# Control_Board.net
KiCad netlist of a schematic drawn in EAGLE
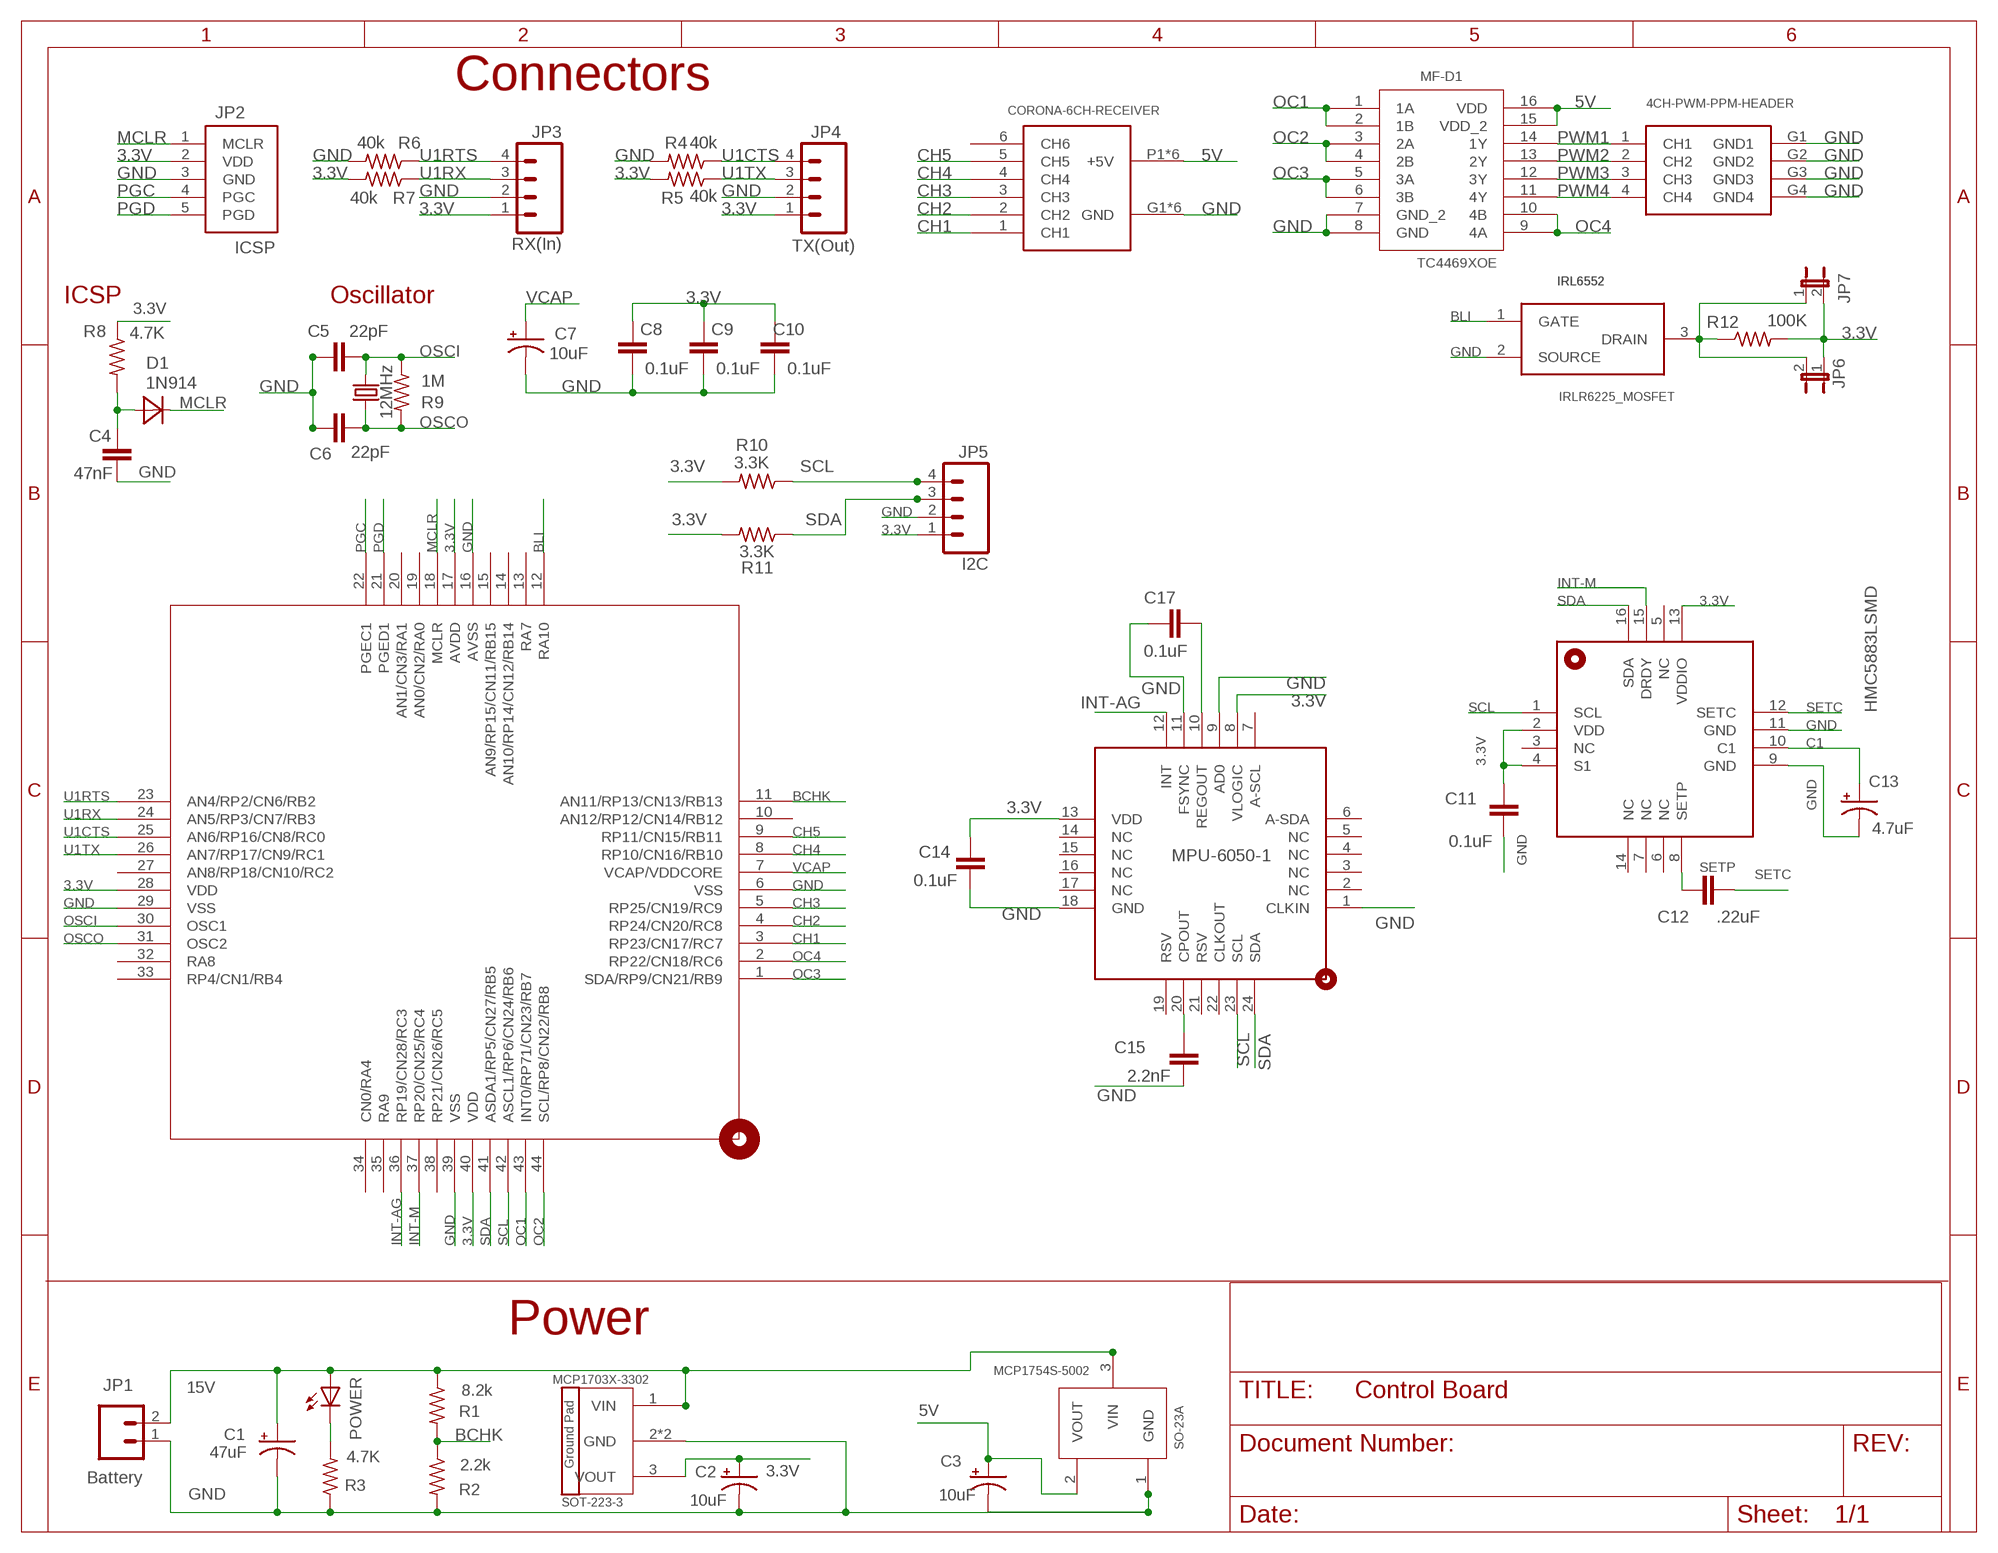
[diagram p0: schematic, sheet 1]

(export (version "E")
  (design (tool "Eeschema 10.0.6"))
  (components
    (comp (ref "C1")
      (value "47uF")
      (footprint "eagle-import:E2-5")
      (libsource (lib "eagle-import") (part "CPOL-USE2-5"))
    )
    (comp (ref "C2")
      (value "10uF")
      (footprint "eagle-import:E2-5")
      (libsource (lib "eagle-import") (part "CPOL-USE2-5"))
    )
    (comp (ref "C3")
      (value "10uF")
      (footprint "eagle-import:E2-5")
      (libsource (lib "eagle-import") (part "CPOL-USE2-5"))
    )
    (comp (ref "C4")
      (value "47nF")
      (footprint "eagle-import:CAP-SMALL-2MM-SMALLPAD")
      (libsource (lib "eagle-import") (part "CAPACITOR"))
    )
    (comp (ref "C5")
      (value "22pF")
      (footprint "eagle-import:CAP-SMALL-2MM-SMALLPAD")
      (libsource (lib "eagle-import") (part "CAPACITOR"))
    )
    (comp (ref "C6")
      (value "22pF")
      (footprint "eagle-import:CAP-SMALL-2MM-SMALLPAD")
      (libsource (lib "eagle-import") (part "CAPACITOR"))
    )
    (comp (ref "C7")
      (value "10uF")
      (footprint "eagle-import:E2-5")
      (libsource (lib "eagle-import") (part "CPOL-USE2-5"))
    )
    (comp (ref "C8")
      (value "0.1uF")
      (footprint "eagle-import:CAP-SMALL-2MM-SMALLPAD")
      (libsource (lib "eagle-import") (part "CAPACITOR"))
    )
    (comp (ref "C9")
      (value "0.1uF")
      (footprint "eagle-import:CAP-SMALL-2MM-SMALLPAD")
      (libsource (lib "eagle-import") (part "CAPACITOR"))
    )
    (comp (ref "C10")
      (value "0.1uF")
      (footprint "eagle-import:CAP-SMALL-2MM-SMALLPAD")
      (libsource (lib "eagle-import") (part "CAPACITOR"))
    )
    (comp (ref "C11")
      (value "0.1uF")
      (footprint "eagle-import:CAP-SMALL-2MM-SMALLPAD")
      (libsource (lib "eagle-import") (part "CAPACITOR"))
    )
    (comp (ref "C12")
      (value ".22uF")
      (footprint "eagle-import:C050-024X044")
      (libsource (lib "eagle-import") (part "C-EU050-024X044"))
    )
    (comp (ref "C13")
      (value "4.7uF")
      (footprint "eagle-import:E2-5")
      (libsource (lib "eagle-import") (part "CPOL-USE2-5"))
    )
    (comp (ref "C14")
      (value "0.1uF")
      (footprint "eagle-import:CAP-SMALL-2MM-SMALLPAD")
      (libsource (lib "eagle-import") (part "CAPACITOR"))
    )
    (comp (ref "C15")
      (value "2.2nF")
      (footprint "eagle-import:CAP-SMALL-2MM-SMALLPAD")
      (libsource (lib "eagle-import") (part "CAPACITOR"))
    )
    (comp (ref "C17")
      (value "0.1uF")
      (footprint "eagle-import:CAP-SMALL-2MM-SMALLPAD")
      (libsource (lib "eagle-import") (part "CAPACITOR"))
    )
    (comp (ref "CR1")
      (value "CORONA-6CH-RECEIVER")
      (footprint "eagle-import:CORONA-6CH-RECEIVER-FOOTPRINT")
      (libsource (lib "eagle-import") (part "CORONA-6CH-RECEIVER"))
    )
    (comp (ref "D1")
      (value "1N914")
      (footprint "eagle-import:DO34-5")
      (libsource (lib "eagle-import") (part "1N914"))
    )
    (comp (ref "IRL6552")
      (value "IRLR6225_MOSFET")
      (footprint "eagle-import:TO252")
      (libsource (lib "eagle-import") (part "IRLR6225_MOSFET"))
    )
    (comp (ref "JP1")
      (value "Battery")
      (footprint "eagle-import:1X02_LONGPADS")
      (libsource (lib "eagle-import") (part "M02"))
    )
    (comp (ref "JP2")
      (value "ICSP")
      (footprint "eagle-import:ICSP_LOCK_LONGPADS")
      (libsource (lib "eagle-import") (part "ICSPPADS"))
    )
    (comp (ref "JP3")
      (value "RX(In)")
      (footprint "eagle-import:1X04_LOCK_LONGPADS")
      (libsource (lib "eagle-import") (part "M04LOCK_LONGPADS"))
    )
    (comp (ref "JP4")
      (value "TX(Out)")
      (footprint "eagle-import:1X04_LOCK_LONGPADS")
      (libsource (lib "eagle-import") (part "M04LOCK_LONGPADS"))
    )
    (comp (ref "JP5")
      (value "I2C")
      (footprint "eagle-import:1X04_LOCK_LONGPADS")
      (libsource (lib "eagle-import") (part "M04LOCK_LONGPADS"))
    )
    (comp (ref "JP6")
      (value "JUMPER-2PTH_LOCK")
      (footprint "eagle-import:1X02_LOCK")
      (libsource (lib "eagle-import") (part "JUMPER-2PTH_LOCK"))
    )
    (comp (ref "JP7")
      (value "JUMPER-2PTH_LOCK")
      (footprint "eagle-import:1X02_LOCK")
      (libsource (lib "eagle-import") (part "JUMPER-2PTH_LOCK"))
    )
    (comp (ref "MCP1703X-3302")
      (value "SOT-223-3")
      (footprint "eagle-import:SOT-223_3MC")
      (libsource (lib "eagle-import") (part "MCP1703X-XXXXX/D"))
    )
    (comp (ref "MCP1754S-5002")
      (value "SO-23A")
      (footprint "eagle-import:SOT-23A_MC")
      (libsource (lib "eagle-import") (part "MCP1703X-XXXXX/C"))
    )
    (comp (ref "MF-D1")
      (value "TC4469XOE")
      (footprint "eagle-import:SOIC16_W_MC")
      (libsource (lib "eagle-import") (part "TC4469XOE"))
    )
    (comp (ref "POWER")
      (value "LED3MM")
      (footprint "eagle-import:LED3MM")
      (libsource (lib "eagle-import") (part "LED3MM"))
    )
    (comp (ref "PWM-PPM")
      (value "4CH-PWM-PPM-HEADER")
      (footprint "eagle-import:4CH-PWM-PPM-HEADER-PACKAGE")
      (libsource (lib "eagle-import") (part "4CH-PWM-PPM-HEADER"))
    )
    (comp (ref "Q1")
      (value "12MHz")
      (footprint "eagle-import:HC49US")
      (libsource (lib "eagle-import") (part "CRYSTALHC49US"))
    )
    (comp (ref "R1")
      (value "8.2k")
      (footprint "eagle-import:0204_7")
      (libsource (lib "eagle-import") (part "R-US_0204/7"))
    )
    (comp (ref "R2")
      (value "2.2k")
      (footprint "eagle-import:0204_7")
      (libsource (lib "eagle-import") (part "R-US_0204/7"))
    )
    (comp (ref "R3")
      (value "4.7K")
      (footprint "eagle-import:0204_7")
      (libsource (lib "eagle-import") (part "R-US_0204/7"))
    )
    (comp (ref "R4")
      (value "40k")
      (footprint "eagle-import:0204_7")
      (libsource (lib "eagle-import") (part "R-US_0204/7"))
    )
    (comp (ref "R5")
      (value "40k")
      (footprint "eagle-import:0204_7")
      (libsource (lib "eagle-import") (part "R-US_0204/7"))
    )
    (comp (ref "R6")
      (value "40k")
      (footprint "eagle-import:0204_7")
      (libsource (lib "eagle-import") (part "R-US_0204/7"))
    )
    (comp (ref "R7")
      (value "40k")
      (footprint "eagle-import:0204_7")
      (libsource (lib "eagle-import") (part "R-US_0204/7"))
    )
    (comp (ref "R8")
      (value "4.7K")
      (footprint "eagle-import:0204_7")
      (libsource (lib "eagle-import") (part "R-US_0204/7"))
    )
    (comp (ref "R9")
      (value "1M")
      (footprint "eagle-import:0204_7")
      (libsource (lib "eagle-import") (part "R-US_0204/7"))
    )
    (comp (ref "R10")
      (value "3.3K")
      (footprint "eagle-import:0204_7")
      (libsource (lib "eagle-import") (part "R-US_0204/7"))
    )
    (comp (ref "R11")
      (value "3.3K")
      (footprint "eagle-import:0204_7")
      (libsource (lib "eagle-import") (part "R-US_0204/7"))
    )
    (comp (ref "R12")
      (value "100K")
      (footprint "eagle-import:0204_7")
      (libsource (lib "eagle-import") (part "R-US_0204/7"))
    )
    (comp (ref "U$1")
      (value "MPU-6050-1")
      (footprint "eagle-import:MPU-6050_QFN-24-4MM2_AZ")
      (libsource (lib "eagle-import") (part "MPU-6050-1"))
    )
    (comp (ref "U$3")
      (value "PIC24HJ128GP204_AZ")
      (footprint "eagle-import:TQFP44_10X10MC")
      (libsource (lib "eagle-import") (part "PIC24HJ128GP204_AZ"))
    )
    (comp (ref "U1")
      (value "HMC5883LSMD")
      (footprint "eagle-import:HMC5883L-16LPCC")
      (libsource (lib "eagle-import") (part "HMC5883LSMD"))
    )
  )
  (nets
    (net (code "1") (name "/3.3V") (class "Default")
      (node (ref "C10") (pin "1") (pinfunction "1_1") (pintype "passive"))
      (node (ref "C11") (pin "2") (pinfunction "2_2") (pintype "passive"))
      (node (ref "C14") (pin "1") (pinfunction "1_1") (pintype "passive"))
      (node (ref "C2") (pin "+") (pinfunction "+_+") (pintype "passive"))
      (node (ref "C8") (pin "1") (pinfunction "1_1") (pintype "passive"))
      (node (ref "C9") (pin "1") (pinfunction "1_1") (pintype "passive"))
      (node (ref "JP2") (pin "2") (pinfunction "VDD_2") (pintype "bidirectional"))
      (node (ref "JP3") (pin "1") (pinfunction "1_1") (pintype "passive"))
      (node (ref "JP4") (pin "1") (pinfunction "1_1") (pintype "passive"))
      (node (ref "JP5") (pin "1") (pinfunction "1_1") (pintype "passive"))
      (node (ref "JP6") (pin "1") (pinfunction "1_1") (pintype "passive"))
      (node (ref "JP7") (pin "2") (pinfunction "2_2") (pintype "passive"))
      (node (ref "MCP1703X-3302") (pin "3") (pinfunction "VOUT_3") (pintype "power_in"))
      (node (ref "R10") (pin "2") (pinfunction "2_2") (pintype "passive"))
      (node (ref "R11") (pin "2") (pinfunction "2_2") (pintype "passive"))
      (node (ref "R12") (pin "2") (pinfunction "2_2") (pintype "passive"))
      (node (ref "R5") (pin "2") (pinfunction "2_2") (pintype "passive"))
      (node (ref "R7") (pin "2") (pinfunction "2_2") (pintype "passive"))
      (node (ref "R8") (pin "1") (pinfunction "1_1") (pintype "passive"))
      (node (ref "U$1") (pin "13") (pinfunction "VDD_13") (pintype "power_in"))
      (node (ref "U$1") (pin "8") (pinfunction "VLOGIC_8") (pintype "bidirectional"))
      (node (ref "U$3") (pin "17") (pinfunction "AVDD_17") (pintype "power_in"))
      (node (ref "U$3") (pin "28") (pinfunction "VDD_28") (pintype "power_in"))
      (node (ref "U$3") (pin "40") (pinfunction "VDD_40") (pintype "power_in"))
      (node (ref "U1") (pin "13") (pinfunction "VDDIO_13") (pintype "power_in"))
      (node (ref "U1") (pin "2") (pinfunction "VDD_2") (pintype "power_in"))
      (node (ref "U1") (pin "4") (pinfunction "S1_4") (pintype "power_in"))
    )
    (net (code "2") (name "/5V") (class "Default")
      (node (ref "C3") (pin "+") (pinfunction "+_+") (pintype "passive"))
      (node (ref "CR1") (pin "P1") (pinfunction "+5V_P1") (pintype "power_in"))
      (node (ref "CR1") (pin "P2") (pinfunction "+5V_P2") (pintype "power_in"))
      (node (ref "CR1") (pin "P3") (pinfunction "+5V_P3") (pintype "power_in"))
      (node (ref "CR1") (pin "P4") (pinfunction "+5V_P4") (pintype "power_in"))
      (node (ref "CR1") (pin "P5") (pinfunction "+5V_P5") (pintype "power_in"))
      (node (ref "CR1") (pin "P6") (pinfunction "+5V_P6") (pintype "power_in"))
      (node (ref "MCP1754S-5002") (pin "2") (pinfunction "VOUT_2") (pintype "power_in"))
      (node (ref "MF-D1") (pin "15") (pinfunction "VDD_2_15") (pintype "passive"))
      (node (ref "MF-D1") (pin "16") (pinfunction "VDD_16") (pintype "passive"))
    )
    (net (code "3") (name "/15V") (class "Default")
      (node (ref "C1") (pin "+") (pinfunction "+_+") (pintype "passive"))
      (node (ref "JP1") (pin "2") (pinfunction "2_2") (pintype "passive"))
      (node (ref "MCP1703X-3302") (pin "1") (pinfunction "VIN_1") (pintype "power_in"))
      (node (ref "MCP1754S-5002") (pin "3") (pinfunction "VIN_3") (pintype "power_in"))
      (node (ref "POWER") (pin "A") (pinfunction "A_A") (pintype "passive"))
      (node (ref "R1") (pin "1") (pinfunction "1_1") (pintype "passive"))
    )
    (net (code "4") (name "/BCHK") (class "Default")
      (node (ref "R1") (pin "2") (pinfunction "2_2") (pintype "passive"))
      (node (ref "R2") (pin "1") (pinfunction "1_1") (pintype "passive"))
      (node (ref "U$3") (pin "11") (pinfunction "AN11/RP13/CN13/RB13_11") (pintype "passive"))
    )
    (net (code "5") (name "/BLI") (class "Default")
      (node (ref "IRL6552") (pin "1") (pinfunction "GATE_1") (pintype "bidirectional"))
      (node (ref "U$3") (pin "12") (pinfunction "RA10_12") (pintype "passive"))
    )
    (net (code "6") (name "/C1") (class "Default")
      (node (ref "C13") (pin "+") (pinfunction "+_+") (pintype "passive"))
      (node (ref "U1") (pin "10") (pinfunction "C1_10") (pintype "passive"))
    )
    (net (code "7") (name "/CH1") (class "Default")
      (node (ref "CR1") (pin "1") (pinfunction "CH1_1") (pintype "bidirectional"))
      (node (ref "U$3") (pin "3") (pinfunction "RP23/CN17/RC7_3") (pintype "passive"))
    )
    (net (code "8") (name "/CH2") (class "Default")
      (node (ref "CR1") (pin "2") (pinfunction "CH2_2") (pintype "bidirectional"))
      (node (ref "U$3") (pin "4") (pinfunction "RP24/CN20/RC8_4") (pintype "passive"))
    )
    (net (code "9") (name "/CH3") (class "Default")
      (node (ref "CR1") (pin "3") (pinfunction "CH3_3") (pintype "bidirectional"))
      (node (ref "U$3") (pin "5") (pinfunction "RP25/CN19/RC9_5") (pintype "passive"))
    )
    (net (code "10") (name "/CH4") (class "Default")
      (node (ref "CR1") (pin "4") (pinfunction "CH4_4") (pintype "bidirectional"))
      (node (ref "U$3") (pin "8") (pinfunction "RP10/CN16/RB10_8") (pintype "passive"))
    )
    (net (code "11") (name "/CH5") (class "Default")
      (node (ref "CR1") (pin "5") (pinfunction "CH5_5") (pintype "bidirectional"))
      (node (ref "U$3") (pin "9") (pinfunction "RP11/CN15/RB11_9") (pintype "passive"))
    )
    (net (code "12") (name "/GND") (class "Default")
      (node (ref "C1") (pin "-") (pinfunction "-_-") (pintype "passive"))
      (node (ref "C10") (pin "2") (pinfunction "2_2") (pintype "passive"))
      (node (ref "C11") (pin "1") (pinfunction "1_1") (pintype "passive"))
      (node (ref "C13") (pin "-") (pinfunction "-_-") (pintype "passive"))
      (node (ref "C14") (pin "2") (pinfunction "2_2") (pintype "passive"))
      (node (ref "C15") (pin "2") (pinfunction "2_2") (pintype "passive"))
      (node (ref "C17") (pin "1") (pinfunction "1_1") (pintype "passive"))
      (node (ref "C2") (pin "-") (pinfunction "-_-") (pintype "passive"))
      (node (ref "C3") (pin "-") (pinfunction "-_-") (pintype "passive"))
      (node (ref "C4") (pin "2") (pinfunction "2_2") (pintype "passive"))
      (node (ref "C5") (pin "1") (pinfunction "1_1") (pintype "passive"))
      (node (ref "C6") (pin "1") (pinfunction "1_1") (pintype "passive"))
      (node (ref "C7") (pin "-") (pinfunction "-_-") (pintype "passive"))
      (node (ref "C8") (pin "2") (pinfunction "2_2") (pintype "passive"))
      (node (ref "C9") (pin "2") (pinfunction "2_2") (pintype "passive"))
      (node (ref "CR1") (pin "G1") (pinfunction "GND_G1") (pintype "power_in"))
      (node (ref "CR1") (pin "G2") (pinfunction "GND_G2") (pintype "power_in"))
      (node (ref "CR1") (pin "G3") (pinfunction "GND_G3") (pintype "power_in"))
      (node (ref "CR1") (pin "G4") (pinfunction "GND_G4") (pintype "power_in"))
      (node (ref "CR1") (pin "G5") (pinfunction "GND_G5") (pintype "power_in"))
      (node (ref "CR1") (pin "G6") (pinfunction "GND_G6") (pintype "power_in"))
      (node (ref "IRL6552") (pin "2") (pinfunction "SOURCE_2") (pintype "bidirectional"))
      (node (ref "JP1") (pin "1") (pinfunction "1_1") (pintype "passive"))
      (node (ref "JP2") (pin "3") (pinfunction "GND_3") (pintype "bidirectional"))
      (node (ref "JP3") (pin "2") (pinfunction "2_2") (pintype "passive"))
      (node (ref "JP4") (pin "2") (pinfunction "2_2") (pintype "passive"))
      (node (ref "JP5") (pin "2") (pinfunction "2_2") (pintype "passive"))
      (node (ref "MCP1703X-3302") (pin "2") (pinfunction "GND_2") (pintype "power_in"))
      (node (ref "MCP1703X-3302") (pin "4") (pinfunction "GND_4") (pintype "power_in"))
      (node (ref "MCP1754S-5002") (pin "1") (pinfunction "GND_1") (pintype "power_in"))
      (node (ref "MF-D1") (pin "7") (pinfunction "GND_2_7") (pintype "passive"))
      (node (ref "MF-D1") (pin "8") (pinfunction "GND_8") (pintype "passive"))
      (node (ref "PWM-PPM") (pin "G1") (pinfunction "GND1_G1") (pintype "power_in"))
      (node (ref "PWM-PPM") (pin "G2") (pinfunction "GND2_G2") (pintype "power_in"))
      (node (ref "PWM-PPM") (pin "G3") (pinfunction "GND3_G3") (pintype "power_in"))
      (node (ref "PWM-PPM") (pin "G4") (pinfunction "GND4_G4") (pintype "power_in"))
      (node (ref "R2") (pin "2") (pinfunction "2_2") (pintype "passive"))
      (node (ref "R3") (pin "1") (pinfunction "1_1") (pintype "passive"))
      (node (ref "R4") (pin "2") (pinfunction "2_2") (pintype "passive"))
      (node (ref "R6") (pin "2") (pinfunction "2_2") (pintype "passive"))
      (node (ref "U$1") (pin "1") (pinfunction "CLKIN_1") (pintype "bidirectional"))
      (node (ref "U$1") (pin "11") (pinfunction "FSYNC_11") (pintype "bidirectional"))
      (node (ref "U$1") (pin "18") (pinfunction "GND_18") (pintype "power_in"))
      (node (ref "U$1") (pin "9") (pinfunction "AD0_9") (pintype "bidirectional"))
      (node (ref "U$3") (pin "16") (pinfunction "AVSS_16") (pintype "power_in"))
      (node (ref "U$3") (pin "29") (pinfunction "VSS_29") (pintype "power_in"))
      (node (ref "U$3") (pin "39") (pinfunction "VSS_39") (pintype "power_in"))
      (node (ref "U$3") (pin "6") (pinfunction "VSS_6") (pintype "power_in"))
      (node (ref "U1") (pin "11") (pinfunction "GND_11") (pintype "power_in"))
      (node (ref "U1") (pin "9") (pinfunction "GND_9") (pintype "power_in"))
    )
    (net (code "13") (name "/INT-AG") (class "Default")
      (node (ref "U$1") (pin "12") (pinfunction "INT_12") (pintype "bidirectional"))
      (node (ref "U$3") (pin "36") (pinfunction "RP19/CN28/RC3_36") (pintype "passive"))
    )
    (net (code "14") (name "/INT-M") (class "Default")
      (node (ref "U$3") (pin "37") (pinfunction "RP20/CN25/RC4_37") (pintype "passive"))
      (node (ref "U1") (pin "15") (pinfunction "DRDY_15") (pintype "output"))
    )
    (net (code "15") (name "/MCLR") (class "Default")
      (node (ref "D1") (pin "C") (pinfunction "C_C") (pintype "passive"))
      (node (ref "JP2") (pin "1") (pinfunction "MCLR_1") (pintype "bidirectional"))
      (node (ref "U$3") (pin "18") (pinfunction "MCLR_18") (pintype "passive"))
    )
    (net (code "16") (name "/OC1") (class "Default")
      (node (ref "MF-D1") (pin "1") (pinfunction "1A_1") (pintype "passive"))
      (node (ref "MF-D1") (pin "2") (pinfunction "1B_2") (pintype "passive"))
      (node (ref "U$3") (pin "43") (pinfunction "INT0/RP71/CN23/RB7_43") (pintype "passive"))
    )
    (net (code "17") (name "/OC2") (class "Default")
      (node (ref "MF-D1") (pin "3") (pinfunction "2A_3") (pintype "passive"))
      (node (ref "MF-D1") (pin "4") (pinfunction "2B_4") (pintype "passive"))
      (node (ref "U$3") (pin "44") (pinfunction "SCL/RP8/CN22/RB8_44") (pintype "passive"))
    )
    (net (code "18") (name "/OC3") (class "Default")
      (node (ref "MF-D1") (pin "5") (pinfunction "3A_5") (pintype "passive"))
      (node (ref "MF-D1") (pin "6") (pinfunction "3B_6") (pintype "passive"))
      (node (ref "U$3") (pin "1") (pinfunction "SDA/RP9/CN21/RB9_1") (pintype "passive"))
    )
    (net (code "19") (name "/OC4") (class "Default")
      (node (ref "MF-D1") (pin "10") (pinfunction "4B_10") (pintype "passive"))
      (node (ref "MF-D1") (pin "9") (pinfunction "4A_9") (pintype "passive"))
      (node (ref "U$3") (pin "2") (pinfunction "RP22/CN18/RC6_2") (pintype "passive"))
    )
    (net (code "20") (name "/OSCI") (class "Default")
      (node (ref "C5") (pin "2") (pinfunction "2_2") (pintype "passive"))
      (node (ref "Q1") (pin "2") (pinfunction "2_2") (pintype "passive"))
      (node (ref "R9") (pin "1") (pinfunction "1_1") (pintype "passive"))
      (node (ref "U$3") (pin "30") (pinfunction "OSC1_30") (pintype "passive"))
    )
    (net (code "21") (name "/OSCO") (class "Default")
      (node (ref "C6") (pin "2") (pinfunction "2_2") (pintype "passive"))
      (node (ref "Q1") (pin "1") (pinfunction "1_1") (pintype "passive"))
      (node (ref "R9") (pin "2") (pinfunction "2_2") (pintype "passive"))
      (node (ref "U$3") (pin "31") (pinfunction "OSC2_31") (pintype "passive"))
    )
    (net (code "22") (name "/PGC") (class "Default")
      (node (ref "JP2") (pin "4") (pinfunction "PGC_4") (pintype "bidirectional"))
      (node (ref "U$3") (pin "22") (pinfunction "PGEC1_22") (pintype "passive"))
    )
    (net (code "23") (name "/PGD") (class "Default")
      (node (ref "JP2") (pin "5") (pinfunction "PGD_5") (pintype "bidirectional"))
      (node (ref "U$3") (pin "21") (pinfunction "PGED1_21") (pintype "passive"))
    )
    (net (code "24") (name "/PWM1") (class "Default")
      (node (ref "MF-D1") (pin "14") (pinfunction "1Y_14") (pintype "passive"))
      (node (ref "PWM-PPM") (pin "1") (pinfunction "CH1_1") (pintype "bidirectional"))
    )
    (net (code "25") (name "/PWM2") (class "Default")
      (node (ref "MF-D1") (pin "13") (pinfunction "2Y_13") (pintype "passive"))
      (node (ref "PWM-PPM") (pin "2") (pinfunction "CH2_2") (pintype "bidirectional"))
    )
    (net (code "26") (name "/PWM3") (class "Default")
      (node (ref "MF-D1") (pin "12") (pinfunction "3Y_12") (pintype "passive"))
      (node (ref "PWM-PPM") (pin "3") (pinfunction "CH3_3") (pintype "bidirectional"))
    )
    (net (code "27") (name "/PWM4") (class "Default")
      (node (ref "MF-D1") (pin "11") (pinfunction "4Y_11") (pintype "passive"))
      (node (ref "PWM-PPM") (pin "4") (pinfunction "CH4_4") (pintype "bidirectional"))
    )
    (net (code "28") (name "/SCL") (class "Default")
      (node (ref "JP5") (pin "4") (pinfunction "4_4") (pintype "passive"))
      (node (ref "R10") (pin "1") (pinfunction "1_1") (pintype "passive"))
      (node (ref "U$1") (pin "23") (pinfunction "SCL_23") (pintype "bidirectional"))
      (node (ref "U$3") (pin "42") (pinfunction "ASCL1/RP6/CN24/RB6_42") (pintype "passive"))
      (node (ref "U1") (pin "1") (pinfunction "SCL_1") (pintype "bidirectional"))
    )
    (net (code "29") (name "/SDA") (class "Default")
      (node (ref "JP5") (pin "3") (pinfunction "3_3") (pintype "passive"))
      (node (ref "R11") (pin "1") (pinfunction "1_1") (pintype "passive"))
      (node (ref "U$1") (pin "24") (pinfunction "SDA_24") (pintype "bidirectional"))
      (node (ref "U$3") (pin "41") (pinfunction "ASDA1/RP5/CN27/RB5_41") (pintype "passive"))
      (node (ref "U1") (pin "16") (pinfunction "SDA_16") (pintype "bidirectional"))
    )
    (net (code "30") (name "/SETC") (class "Default")
      (node (ref "C12") (pin "2") (pinfunction "2_2") (pintype "passive"))
      (node (ref "U1") (pin "12") (pinfunction "SETC_12") (pintype "passive"))
    )
    (net (code "31") (name "/SETP") (class "Default")
      (node (ref "C12") (pin "1") (pinfunction "1_1") (pintype "passive"))
      (node (ref "U1") (pin "8") (pinfunction "SETP_8") (pintype "passive"))
    )
    (net (code "32") (name "/U1CTS") (class "Default")
      (node (ref "JP4") (pin "4") (pinfunction "4_4") (pintype "passive"))
      (node (ref "R4") (pin "1") (pinfunction "1_1") (pintype "passive"))
      (node (ref "U$3") (pin "25") (pinfunction "AN6/RP16/CN8/RC0_25") (pintype "passive"))
    )
    (net (code "33") (name "/U1RTS") (class "Default")
      (node (ref "JP3") (pin "4") (pinfunction "4_4") (pintype "passive"))
      (node (ref "R6") (pin "1") (pinfunction "1_1") (pintype "passive"))
      (node (ref "U$3") (pin "23") (pinfunction "AN4/RP2/CN6/RB2_23") (pintype "passive"))
    )
    (net (code "34") (name "/U1RX") (class "Default")
      (node (ref "JP3") (pin "3") (pinfunction "3_3") (pintype "passive"))
      (node (ref "R7") (pin "1") (pinfunction "1_1") (pintype "passive"))
      (node (ref "U$3") (pin "24") (pinfunction "AN5/RP3/CN7/RB3_24") (pintype "passive"))
    )
    (net (code "35") (name "/U1TX") (class "Default")
      (node (ref "JP4") (pin "3") (pinfunction "3_3") (pintype "passive"))
      (node (ref "R5") (pin "1") (pinfunction "1_1") (pintype "passive"))
      (node (ref "U$3") (pin "26") (pinfunction "AN7/RP17/CN9/RC1_26") (pintype "passive"))
    )
    (net (code "36") (name "/VCAP") (class "Default")
      (node (ref "C7") (pin "+") (pinfunction "+_+") (pintype "passive"))
      (node (ref "U$3") (pin "7") (pinfunction "VCAP/VDDCORE_7") (pintype "passive"))
    )
    (net (code "37") (name "Net-(C4-Pad1)") (class "Default")
      (node (ref "C4") (pin "1") (pinfunction "1_1") (pintype "passive"))
      (node (ref "D1") (pin "A") (pinfunction "A_A") (pintype "passive"))
      (node (ref "R8") (pin "2") (pinfunction "2_2") (pintype "passive"))
    )
    (net (code "38") (name "Net-(IRL6552-DRAIN)") (class "Default")
      (node (ref "IRL6552") (pin "3") (pinfunction "DRAIN_3") (pintype "bidirectional"))
      (node (ref "JP6") (pin "2") (pinfunction "2_2") (pintype "passive"))
      (node (ref "JP7") (pin "1") (pinfunction "1_1") (pintype "passive"))
      (node (ref "R12") (pin "1") (pinfunction "1_1") (pintype "passive"))
    )
    (net (code "39") (name "Net-(POWER-C)") (class "Default")
      (node (ref "POWER") (pin "K") (pinfunction "C_K") (pintype "passive"))
      (node (ref "R3") (pin "2") (pinfunction "2_2") (pintype "passive"))
    )
    (net (code "40") (name "Net-(U$1-CPOUT)") (class "Default")
      (node (ref "C15") (pin "1") (pinfunction "1_1") (pintype "passive"))
      (node (ref "U$1") (pin "20") (pinfunction "CPOUT_20") (pintype "bidirectional"))
    )
    (net (code "41") (name "Net-(U$1-REGOUT)") (class "Default")
      (node (ref "C17") (pin "2") (pinfunction "2_2") (pintype "passive"))
      (node (ref "U$1") (pin "10") (pinfunction "REGOUT_10") (pintype "bidirectional"))
    )
    (net (code "42") (name "unconnected-(CR1-CH6-Pad6)") (class "Default")
      (node (ref "CR1") (pin "6") (pinfunction "CH6_6") (pintype "bidirectional"))
    )
    (net (code "43") (name "unconnected-(U$1-A-SCL-Pad7)") (class "Default")
      (node (ref "U$1") (pin "7") (pinfunction "A-SCL_7") (pintype "bidirectional"))
    )
    (net (code "44") (name "unconnected-(U$1-A-SDA-Pad6)") (class "Default")
      (node (ref "U$1") (pin "6") (pinfunction "A-SDA_6") (pintype "bidirectional"))
    )
    (net (code "45") (name "unconnected-(U$1-CLKOUT-Pad22)") (class "Default")
      (node (ref "U$1") (pin "22") (pinfunction "CLKOUT_22") (pintype "bidirectional"))
    )
    (net (code "46") (name "unconnected-(U$1-NC-Pad2)") (class "Default")
      (node (ref "U$1") (pin "2") (pinfunction "NC_2") (pintype "no_connect"))
    )
    (net (code "47") (name "unconnected-(U$1-NC-Pad3)") (class "Default")
      (node (ref "U$1") (pin "3") (pinfunction "NC_3") (pintype "no_connect"))
    )
    (net (code "48") (name "unconnected-(U$1-NC-Pad4)") (class "Default")
      (node (ref "U$1") (pin "4") (pinfunction "NC_4") (pintype "no_connect"))
    )
    (net (code "49") (name "unconnected-(U$1-NC-Pad5)") (class "Default")
      (node (ref "U$1") (pin "5") (pinfunction "NC_5") (pintype "no_connect"))
    )
    (net (code "50") (name "unconnected-(U$1-NC-Pad14)") (class "Default")
      (node (ref "U$1") (pin "14") (pinfunction "NC_14") (pintype "no_connect"))
    )
    (net (code "51") (name "unconnected-(U$1-NC-Pad15)") (class "Default")
      (node (ref "U$1") (pin "15") (pinfunction "NC_15") (pintype "no_connect"))
    )
    (net (code "52") (name "unconnected-(U$1-NC-Pad16)") (class "Default")
      (node (ref "U$1") (pin "16") (pinfunction "NC_16") (pintype "no_connect"))
    )
    (net (code "53") (name "unconnected-(U$1-NC-Pad17)") (class "Default")
      (node (ref "U$1") (pin "17") (pinfunction "NC_17") (pintype "no_connect"))
    )
    (net (code "54") (name "unconnected-(U$1-RSV-Pad19)") (class "Default")
      (node (ref "U$1") (pin "19") (pinfunction "RSV_19") (pintype "no_connect"))
    )
    (net (code "55") (name "unconnected-(U$1-RSV-Pad21)") (class "Default")
      (node (ref "U$1") (pin "21") (pinfunction "RSV_21") (pintype "no_connect"))
    )
    (net (code "56") (name "unconnected-(U$3-AN0{slash}CN2{slash}RA0-Pad19)") (class "Default")
      (node (ref "U$3") (pin "19") (pinfunction "AN0/CN2/RA0_19") (pintype "passive"))
    )
    (net (code "57") (name "unconnected-(U$3-AN1{slash}CN3{slash}RA1-Pad20)") (class "Default")
      (node (ref "U$3") (pin "20") (pinfunction "AN1/CN3/RA1_20") (pintype "passive"))
    )
    (net (code "58") (name "unconnected-(U$3-AN8{slash}RP18{slash}CN10{slash}RC2-Pad27)") (class "Default")
      (node (ref "U$3") (pin "27") (pinfunction "AN8/RP18/CN10/RC2_27") (pintype "passive"))
    )
    (net (code "59") (name "unconnected-(U$3-AN9{slash}RP15{slash}CN11{slash}RB15-Pad15)") (class "Default")
      (node (ref "U$3") (pin "15") (pinfunction "AN9/RP15/CN11/RB15_15") (pintype "passive"))
    )
    (net (code "60") (name "unconnected-(U$3-AN10{slash}RP14{slash}CN12{slash}RB14-Pad14)") (class "Default")
      (node (ref "U$3") (pin "14") (pinfunction "AN10/RP14/CN12/RB14_14") (pintype "passive"))
    )
    (net (code "61") (name "unconnected-(U$3-AN12{slash}RP12{slash}CN14{slash}RB12-Pad10)") (class "Default")
      (node (ref "U$3") (pin "10") (pinfunction "AN12/RP12/CN14/RB12_10") (pintype "passive"))
    )
    (net (code "62") (name "unconnected-(U$3-CN0{slash}RA4-Pad34)") (class "Default")
      (node (ref "U$3") (pin "34") (pinfunction "CN0/RA4_34") (pintype "passive"))
    )
    (net (code "63") (name "unconnected-(U$3-RA7-Pad13)") (class "Default")
      (node (ref "U$3") (pin "13") (pinfunction "RA7_13") (pintype "passive"))
    )
    (net (code "64") (name "unconnected-(U$3-RA8-Pad32)") (class "Default")
      (node (ref "U$3") (pin "32") (pinfunction "RA8_32") (pintype "passive"))
    )
    (net (code "65") (name "unconnected-(U$3-RA9-Pad35)") (class "Default")
      (node (ref "U$3") (pin "35") (pinfunction "RA9_35") (pintype "passive"))
    )
    (net (code "66") (name "unconnected-(U$3-RP4{slash}CN1{slash}RB4-Pad33)") (class "Default")
      (node (ref "U$3") (pin "33") (pinfunction "RP4/CN1/RB4_33") (pintype "passive"))
    )
    (net (code "67") (name "unconnected-(U$3-RP21{slash}CN26{slash}RC5-Pad38)") (class "Default")
      (node (ref "U$3") (pin "38") (pinfunction "RP21/CN26/RC5_38") (pintype "passive"))
    )
    (net (code "68") (name "unconnected-(U1-NC-Pad3)") (class "Default")
      (node (ref "U1") (pin "3") (pinfunction "NC_3") (pintype "no_connect"))
    )
    (net (code "69") (name "unconnected-(U1-NC-Pad5)") (class "Default")
      (node (ref "U1") (pin "5") (pinfunction "NC_5") (pintype "no_connect"))
    )
    (net (code "70") (name "unconnected-(U1-NC-Pad6)") (class "Default")
      (node (ref "U1") (pin "6") (pinfunction "NC_6") (pintype "no_connect"))
    )
    (net (code "71") (name "unconnected-(U1-NC-Pad7)") (class "Default")
      (node (ref "U1") (pin "7") (pinfunction "NC_7") (pintype "no_connect"))
    )
    (net (code "72") (name "unconnected-(U1-NC-Pad14)") (class "Default")
      (node (ref "U1") (pin "14") (pinfunction "NC_14") (pintype "no_connect"))
    )
  )
)
